# Transponder_LED.net
KiCad netlist of a schematic drawn in EAGLE
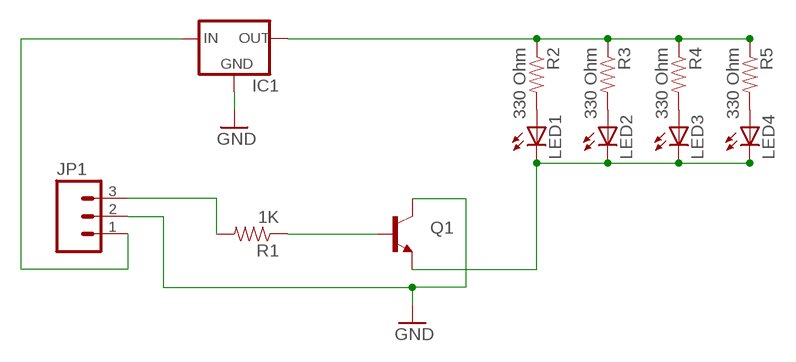
[diagram p0: schematic, sheet 1]

(export (version "E")
  (design (tool "Eeschema 10.0.6"))
  (components
    (comp (ref "IC1")
      (value "V_REG_78XXTO-92")
      (footprint "eagle-import:TO-92")
      (libsource (lib "eagle-import") (part "V_REG_78XXTO-92"))
    )
    (comp (ref "JP1")
      (value "M03JST-PTH")
      (footprint "eagle-import:JST-3-PTH")
      (libsource (lib "eagle-import") (part "M03JST-PTH"))
    )
    (comp (ref "LED1")
      (value "LED5MM")
      (footprint "eagle-import:LED5MM")
      (libsource (lib "eagle-import") (part "LED5MM"))
    )
    (comp (ref "LED2")
      (value "LED5MM")
      (footprint "eagle-import:LED5MM")
      (libsource (lib "eagle-import") (part "LED5MM"))
    )
    (comp (ref "LED3")
      (value "LED5MM")
      (footprint "eagle-import:LED5MM")
      (libsource (lib "eagle-import") (part "LED5MM"))
    )
    (comp (ref "LED4")
      (value "LED5MM")
      (footprint "eagle-import:LED5MM")
      (libsource (lib "eagle-import") (part "LED5MM"))
    )
    (comp (ref "Q1")
      (value "TRANSISTOR_NPNTO92")
      (footprint "eagle-import:TO-92")
      (libsource (lib "eagle-import") (part "TRANSISTOR_NPNTO92"))
    )
    (comp (ref "R1")
      (value "1K")
      (footprint "eagle-import:AXIAL-0.4")
      (libsource (lib "eagle-import") (part "RESISTORPTH-1/4W"))
    )
    (comp (ref "R2")
      (value "330 Ohm")
      (footprint "eagle-import:AXIAL-0.4")
      (libsource (lib "eagle-import") (part "RESISTORPTH-1/4W"))
    )
    (comp (ref "R3")
      (value "330 Ohm")
      (footprint "eagle-import:AXIAL-0.4")
      (libsource (lib "eagle-import") (part "RESISTORPTH-1/4W"))
    )
    (comp (ref "R4")
      (value "330 Ohm")
      (footprint "eagle-import:AXIAL-0.4")
      (libsource (lib "eagle-import") (part "RESISTORPTH-1/4W"))
    )
    (comp (ref "R5")
      (value "330 Ohm")
      (footprint "eagle-import:AXIAL-0.4")
      (libsource (lib "eagle-import") (part "RESISTORPTH-1/4W"))
    )
  )
  (nets
    (net (code "1") (name "GND") (class "Default")
      (node (ref "IC1") (pin "1") (pinfunction "GND_1") (pintype "input"))
      (node (ref "JP1") (pin "2") (pinfunction "2_2") (pintype "passive"))
      (node (ref "Q1") (pin "3") (pinfunction "C_3") (pintype "passive"))
    )
    (net (code "2") (name "Net-(IC1-IN)") (class "Default")
      (node (ref "IC1") (pin "2") (pinfunction "IN_2") (pintype "input"))
      (node (ref "JP1") (pin "1") (pinfunction "1_1") (pintype "passive"))
    )
    (net (code "3") (name "Net-(IC1-OUT)") (class "Default")
      (node (ref "IC1") (pin "3") (pinfunction "OUT_3") (pintype "output"))
      (node (ref "R2") (pin "P$1") (pinfunction "1_P$1") (pintype "passive"))
      (node (ref "R3") (pin "P$1") (pinfunction "1_P$1") (pintype "passive"))
      (node (ref "R4") (pin "P$1") (pinfunction "1_P$1") (pintype "passive"))
      (node (ref "R5") (pin "P$1") (pinfunction "1_P$1") (pintype "passive"))
    )
    (net (code "4") (name "Net-(LED1-C)") (class "Default")
      (node (ref "LED1") (pin "K") (pinfunction "C_K") (pintype "passive"))
      (node (ref "LED2") (pin "K") (pinfunction "C_K") (pintype "passive"))
      (node (ref "LED3") (pin "K") (pinfunction "C_K") (pintype "passive"))
      (node (ref "LED4") (pin "K") (pinfunction "C_K") (pintype "passive"))
      (node (ref "Q1") (pin "1") (pinfunction "E_1") (pintype "passive"))
    )
    (net (code "5") (name "Net-(Q1-B)") (class "Default")
      (node (ref "Q1") (pin "2") (pinfunction "B_2") (pintype "passive"))
      (node (ref "R1") (pin "P$1") (pinfunction "1_P$1") (pintype "passive"))
    )
    (net (code "6") (name "Net-(R1-2)") (class "Default")
      (node (ref "JP1") (pin "3") (pinfunction "3_3") (pintype "passive"))
      (node (ref "R1") (pin "P$2") (pinfunction "2_P$2") (pintype "passive"))
    )
    (net (code "7") (name "Net-(R2-2)") (class "Default")
      (node (ref "LED1") (pin "A") (pinfunction "A_A") (pintype "passive"))
      (node (ref "R2") (pin "P$2") (pinfunction "2_P$2") (pintype "passive"))
    )
    (net (code "8") (name "Net-(R3-2)") (class "Default")
      (node (ref "LED2") (pin "A") (pinfunction "A_A") (pintype "passive"))
      (node (ref "R3") (pin "P$2") (pinfunction "2_P$2") (pintype "passive"))
    )
    (net (code "9") (name "Net-(R4-2)") (class "Default")
      (node (ref "LED3") (pin "A") (pinfunction "A_A") (pintype "passive"))
      (node (ref "R4") (pin "P$2") (pinfunction "2_P$2") (pintype "passive"))
    )
    (net (code "10") (name "Net-(R5-2)") (class "Default")
      (node (ref "LED4") (pin "A") (pinfunction "A_A") (pintype "passive"))
      (node (ref "R5") (pin "P$2") (pinfunction "2_P$2") (pintype "passive"))
    )
  )
)
